# Interface.net
KiCad netlist of a schematic drawn in Altium Designer
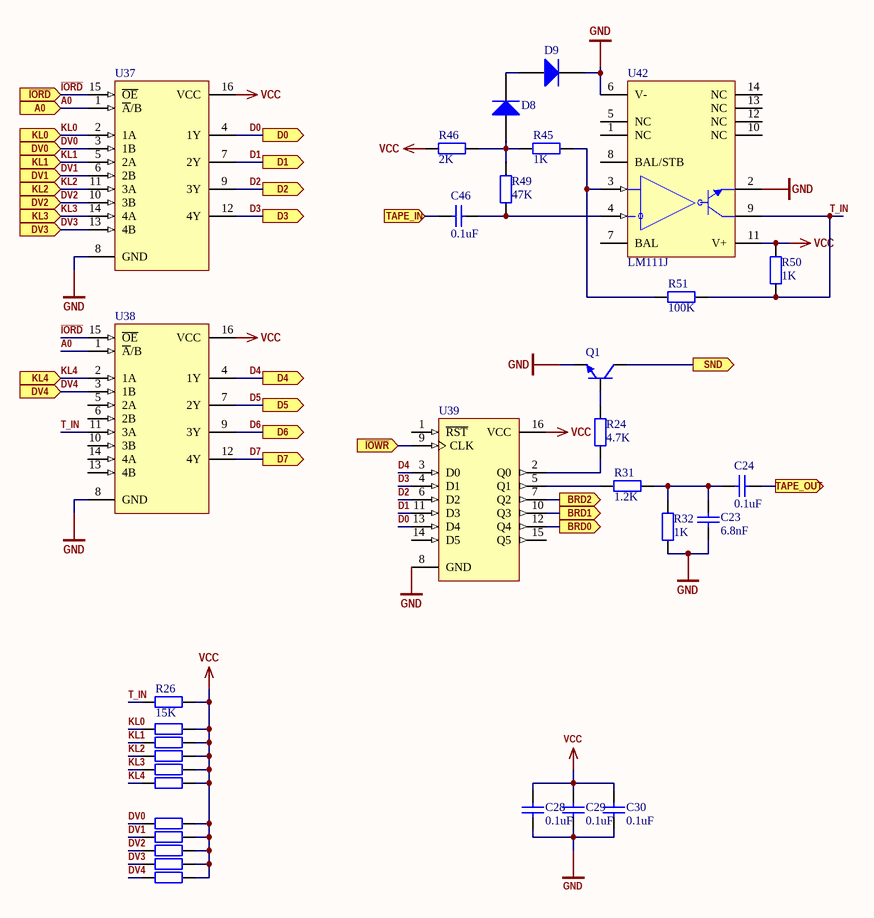
[diagram p0: Interface.SchDoc]

(export (version "E")
  (design (tool "Eeschema 10.0.6"))
  (components
    (comp (ref "C23")
      (value "6.8nF")
      (footprint "RAD-0.3")
      (description "Capacitor")
      (fields (field (name "Comment") "Cap") (field (name "PUBLISHER") "Altium Limited"))
      (libsource (lib "Lenin") (part "Cap"))
    )
    (comp (ref "C24")
      (value "0.1uF")
      (footprint "RAD-0.3")
      (description "Capacitor")
      (fields (field (name "Comment") "Cap") (field (name "PUBLISHER") "Altium Limited"))
      (libsource (lib "Lenin") (part "Cap"))
    )
    (comp (ref "C28")
      (value "0.1uF")
      (footprint "RAD-0.3")
      (description "Capacitor")
      (fields (field (name "Comment") "Cap") (field (name "PUBLISHER") "Altium Limited"))
      (libsource (lib "Lenin") (part "Cap"))
    )
    (comp (ref "C29")
      (value "0.1uF")
      (footprint "RAD-0.3")
      (description "Capacitor")
      (fields (field (name "Comment") "Cap") (field (name "PUBLISHER") "Altium Limited"))
      (libsource (lib "Lenin") (part "Cap"))
    )
    (comp (ref "C30")
      (value "0.1uF")
      (footprint "RAD-0.3")
      (description "Capacitor")
      (fields (field (name "Comment") "Cap") (field (name "PUBLISHER") "Altium Limited"))
      (libsource (lib "Lenin") (part "Cap"))
    )
    (comp (ref "C46")
      (value "0.1uF")
      (footprint "RAD-0.3")
      (description "Capacitor")
      (fields (field (name "Comment") "Cap") (field (name "PUBLISHER") "Altium Limited"))
      (libsource (lib "Lenin") (part "Cap"))
    )
    (comp (ref "D8")
      (value "Diode 1N4148")
      (footprint "DO-35")
      (description "High Conductance Fast Diode")
      (fields (field (name "PUBLISHER") "Altium Limited"))
      (libsource (lib "Miscellaneous Devices") (part "Diode 1N4148"))
    )
    (comp (ref "D9")
      (value "Diode 1N4148")
      (footprint "DO-35")
      (description "High Conductance Fast Diode")
      (fields (field (name "PUBLISHER") "Altium Limited"))
      (libsource (lib "Miscellaneous Devices") (part "Diode 1N4148"))
    )
    (comp (ref "Q1")
      (value "KT315")
      (footprint "Lenin:D35")
      (description "NPN General Purpose Amplifier")
      (fields (field (name "PUBLISHER") "Altium Limited"))
      (libsource (lib "Lenin") (part "KT315"))
    )
    (comp (ref "R24")
      (value "4.7K")
      (footprint "Lenin:AXIAL-0.4")
      (description "Resistor")
      (fields (field (name "Comment") "Res2") (field (name "PUBLISHER") "Altium Limited"))
      (libsource (lib "") (part "Res2_1"))
    )
    (comp (ref "R26")
      (value "15K")
      (footprint "Lenin:AXIAL-0.4")
      (description "Resistor")
      (fields (field (name "Comment") "Res2") (field (name "PUBLISHER") "Altium Limited"))
      (libsource (lib "Lenin") (part "Res2"))
    )
    (comp (ref "R27")
      (value "Res2")
      (footprint "Lenin:AXIAL-0.4")
      (description "Resistor")
      (fields (field (name "PUBLISHER") "Altium Limited"))
      (libsource (lib "Lenin") (part "Res2"))
    )
    (comp (ref "R28")
      (value "Res2")
      (footprint "Lenin:AXIAL-0.4")
      (description "Resistor")
      (fields (field (name "PUBLISHER") "Altium Limited"))
      (libsource (lib "Lenin") (part "Res2"))
    )
    (comp (ref "R29")
      (value "Res2")
      (footprint "Lenin:AXIAL-0.4")
      (description "Resistor")
      (fields (field (name "PUBLISHER") "Altium Limited"))
      (libsource (lib "Lenin") (part "Res2"))
    )
    (comp (ref "R30")
      (value "Res2")
      (footprint "Lenin:AXIAL-0.4")
      (description "Resistor")
      (fields (field (name "PUBLISHER") "Altium Limited"))
      (libsource (lib "Lenin") (part "Res2"))
    )
    (comp (ref "R31")
      (value "1.2K")
      (footprint "Lenin:AXIAL-0.4")
      (description "Resistor")
      (fields (field (name "Comment") "Res2") (field (name "PUBLISHER") "Altium Limited"))
      (libsource (lib "Lenin") (part "Res2"))
    )
    (comp (ref "R32")
      (value "1K")
      (footprint "Lenin:AXIAL-0.4")
      (description "Resistor")
      (fields (field (name "Comment") "Res2") (field (name "PUBLISHER") "Altium Limited"))
      (libsource (lib "") (part "Res2_1"))
    )
    (comp (ref "R33")
      (value "Res2")
      (footprint "Lenin:AXIAL-0.4")
      (description "Resistor")
      (fields (field (name "PUBLISHER") "Altium Limited"))
      (libsource (lib "Lenin") (part "Res2"))
    )
    (comp (ref "R36")
      (value "Res2")
      (footprint "Lenin:AXIAL-0.4")
      (description "Resistor")
      (fields (field (name "PUBLISHER") "Altium Limited"))
      (libsource (lib "Lenin") (part "Res2"))
    )
    (comp (ref "R38")
      (value "Res2")
      (footprint "Lenin:AXIAL-0.4")
      (description "Resistor")
      (fields (field (name "PUBLISHER") "Altium Limited"))
      (libsource (lib "Lenin") (part "Res2"))
    )
    (comp (ref "R40")
      (value "Res2")
      (footprint "Lenin:AXIAL-0.4")
      (description "Resistor")
      (fields (field (name "PUBLISHER") "Altium Limited"))
      (libsource (lib "Lenin") (part "Res2"))
    )
    (comp (ref "R42")
      (value "Res2")
      (footprint "Lenin:AXIAL-0.4")
      (description "Resistor")
      (fields (field (name "PUBLISHER") "Altium Limited"))
      (libsource (lib "Lenin") (part "Res2"))
    )
    (comp (ref "R44")
      (value "Res2")
      (footprint "Lenin:AXIAL-0.4")
      (description "Resistor")
      (fields (field (name "PUBLISHER") "Altium Limited"))
      (libsource (lib "Lenin") (part "Res2"))
    )
    (comp (ref "R45")
      (value "1K")
      (footprint "Lenin:AXIAL-0.4")
      (description "Resistor")
      (fields (field (name "Comment") "Res2") (field (name "PUBLISHER") "Altium Limited"))
      (libsource (lib "") (part "Res2_2"))
    )
    (comp (ref "R46")
      (value "2K")
      (footprint "Lenin:AXIAL-0.4")
      (description "Resistor")
      (fields (field (name "Comment") "Res2") (field (name "PUBLISHER") "Altium Limited"))
      (libsource (lib "") (part "Res2_2"))
    )
    (comp (ref "R49")
      (value "47K")
      (footprint "Lenin:AXIAL-0.4")
      (description "Resistor")
      (fields (field (name "Comment") "Res2") (field (name "PUBLISHER") "Altium Limited"))
      (libsource (lib "Lenin") (part "Res2"))
    )
    (comp (ref "R50")
      (value "1K")
      (footprint "Lenin:AXIAL-0.4")
      (description "Resistor")
      (fields (field (name "Comment") "Res2") (field (name "PUBLISHER") "Altium Limited"))
      (libsource (lib "Lenin") (part "Res2"))
    )
    (comp (ref "R51")
      (value "100K")
      (footprint "Lenin:AXIAL-0.4")
      (description "Resistor")
      (fields (field (name "Comment") "Res2") (field (name "PUBLISHER") "Altium Limited"))
      (libsource (lib "") (part "Res2_2"))
    )
    (comp (ref "U37")
      (value "~")
      (footprint "N016")
      (description "Quadruple 2-Line to 1-Line Data Selector/Multiplexer with 3-State Outputs")
      (fields (field (name "PUBLISHER") "Altium Limited"))
      (libsource (lib "TI Logic Multiplexer") (part "SN74HC257N"))
    )
    (comp (ref "U38")
      (value "~")
      (footprint "N016")
      (description "Quadruple 2-Line to 1-Line Data Selector/Multiplexer with 3-State Outputs")
      (fields (field (name "PUBLISHER") "Altium Limited"))
      (libsource (lib "TI Logic Multiplexer") (part "SN74HC257N"))
    )
    (comp (ref "U39")
      (value "~")
      (footprint "N016")
      (description "Hex D-Type Flip-Flop with Clear")
      (fields (field (name "PUBLISHER") "Altium Limited"))
      (libsource (lib "TI Logic Flip-Flop") (part "SN74HC174N"))
    )
    (comp (ref "U42")
      (value "LM111J")
      (footprint "J014")
      (description "Differential Comparator with Strobe")
      (fields (field (name "PUBLISHER") "Altium Limited"))
      (libsource (lib "TI Analog Comparator") (part "LM111J"))
    )
  )
  (nets
    (net (code "1") (name "/A0") (class "Default")
      (node (ref "U37") (pin "1") (pinfunction "~{A}/B_1") (pintype "input"))
      (node (ref "U38") (pin "1") (pinfunction "~{A}/B_1") (pintype "input"))
    )
    (net (code "2") (name "/BRD0") (class "Default")
      (node (ref "U39") (pin "12") (pinfunction "Q4_12") (pintype "output"))
    )
    (net (code "3") (name "/BRD1") (class "Default")
      (node (ref "U39") (pin "10") (pinfunction "Q3_10") (pintype "output"))
    )
    (net (code "4") (name "/BRD2") (class "Default")
      (node (ref "U39") (pin "7") (pinfunction "Q2_7") (pintype "output"))
    )
    (net (code "5") (name "/D0") (class "Default")
      (node (ref "U37") (pin "4") (pinfunction "1Y_4") (pintype "tri_state"))
      (node (ref "U39") (pin "13") (pinfunction "D4_13") (pintype "input"))
    )
    (net (code "6") (name "/D1") (class "Default")
      (node (ref "U37") (pin "7") (pinfunction "2Y_7") (pintype "tri_state"))
      (node (ref "U39") (pin "11") (pinfunction "D3_11") (pintype "input"))
    )
    (net (code "7") (name "/D2") (class "Default")
      (node (ref "U37") (pin "9") (pinfunction "3Y_9") (pintype "tri_state"))
      (node (ref "U39") (pin "6") (pinfunction "D2_6") (pintype "input"))
    )
    (net (code "8") (name "/D3") (class "Default")
      (node (ref "U37") (pin "12") (pinfunction "4Y_12") (pintype "tri_state"))
      (node (ref "U39") (pin "4") (pinfunction "D1_4") (pintype "input"))
    )
    (net (code "9") (name "/D4") (class "Default")
      (node (ref "U38") (pin "4") (pinfunction "1Y_4") (pintype "tri_state"))
      (node (ref "U39") (pin "3") (pinfunction "D0_3") (pintype "input"))
    )
    (net (code "10") (name "/D5") (class "Default")
      (node (ref "U38") (pin "7") (pinfunction "2Y_7") (pintype "tri_state"))
    )
    (net (code "11") (name "/D6") (class "Default")
      (node (ref "U38") (pin "9") (pinfunction "3Y_9") (pintype "tri_state"))
    )
    (net (code "12") (name "/D7") (class "Default")
      (node (ref "U38") (pin "12") (pinfunction "4Y_12") (pintype "tri_state"))
    )
    (net (code "13") (name "/DV0") (class "Default")
      (node (ref "R36") (pin "1") (pinfunction "1_1") (pintype "passive"))
      (node (ref "U37") (pin "3") (pinfunction "1B_3") (pintype "input"))
    )
    (net (code "14") (name "/DV1") (class "Default")
      (node (ref "R38") (pin "1") (pinfunction "1_1") (pintype "passive"))
      (node (ref "U37") (pin "6") (pinfunction "2B_6") (pintype "input"))
    )
    (net (code "15") (name "/DV2") (class "Default")
      (node (ref "R40") (pin "1") (pinfunction "1_1") (pintype "passive"))
      (node (ref "U37") (pin "10") (pinfunction "3B_10") (pintype "input"))
    )
    (net (code "16") (name "/DV3") (class "Default")
      (node (ref "R42") (pin "1") (pinfunction "1_1") (pintype "passive"))
      (node (ref "U37") (pin "13") (pinfunction "4B_13") (pintype "input"))
    )
    (net (code "17") (name "/DV4") (class "Default")
      (node (ref "R44") (pin "1") (pinfunction "1_1") (pintype "passive"))
      (node (ref "U38") (pin "3") (pinfunction "1B_3") (pintype "input"))
    )
    (net (code "18") (name "/KL0") (class "Default")
      (node (ref "R27") (pin "1") (pinfunction "1_1") (pintype "passive"))
      (node (ref "U37") (pin "2") (pinfunction "1A_2") (pintype "input"))
    )
    (net (code "19") (name "/KL1") (class "Default")
      (node (ref "R28") (pin "1") (pinfunction "1_1") (pintype "passive"))
      (node (ref "U37") (pin "5") (pinfunction "2A_5") (pintype "input"))
    )
    (net (code "20") (name "/KL2") (class "Default")
      (node (ref "R29") (pin "1") (pinfunction "1_1") (pintype "passive"))
      (node (ref "U37") (pin "11") (pinfunction "3A_11") (pintype "input"))
    )
    (net (code "21") (name "/KL3") (class "Default")
      (node (ref "R30") (pin "1") (pinfunction "1_1") (pintype "passive"))
      (node (ref "U37") (pin "14") (pinfunction "4A_14") (pintype "input"))
    )
    (net (code "22") (name "/KL4") (class "Default")
      (node (ref "R33") (pin "1") (pinfunction "1_1") (pintype "passive"))
      (node (ref "U38") (pin "2") (pinfunction "1A_2") (pintype "input"))
    )
    (net (code "23") (name "/SND") (class "Default")
      (node (ref "Q1") (pin "2") (pinfunction "C_2") (pintype "passive"))
    )
    (net (code "24") (name "/TAPE_IN") (class "Default")
      (node (ref "C46") (pin "1") (pinfunction "1_1") (pintype "passive"))
    )
    (net (code "25") (name "/TAPE_OUT") (class "Default")
      (node (ref "C24") (pin "1") (pinfunction "1_1") (pintype "passive"))
    )
    (net (code "26") (name "/T_IN") (class "Default")
      (node (ref "R26") (pin "1") (pinfunction "1_1") (pintype "passive"))
      (node (ref "R50") (pin "1") (pinfunction "1_1") (pintype "passive"))
      (node (ref "R51") (pin "1") (pinfunction "1_1") (pintype "passive"))
      (node (ref "U38") (pin "11") (pinfunction "3A_11") (pintype "input"))
      (node (ref "U42") (pin "9") (pinfunction "COL_OUT_9") (pintype "passive"))
    )
    (net (code "27") (name "/~{IORD}") (class "Default")
      (node (ref "U37") (pin "15") (pinfunction "~{OE}_15") (pintype "input"))
      (node (ref "U38") (pin "15") (pinfunction "~{OE}_15") (pintype "input"))
    )
    (net (code "28") (name "/~{IOWR}") (class "Default")
      (node (ref "U39") (pin "9") (pinfunction "CLK_9") (pintype "input"))
    )
    (net (code "29") (name "GND") (class "Default")
      (node (ref "C23") (pin "1") (pinfunction "1_1") (pintype "passive"))
      (node (ref "C28") (pin "1") (pinfunction "1_1") (pintype "passive"))
      (node (ref "C29") (pin "1") (pinfunction "1_1") (pintype "passive"))
      (node (ref "C30") (pin "1") (pinfunction "1_1") (pintype "passive"))
      (node (ref "D9") (pin "2") (pinfunction "K_2") (pintype "passive"))
      (node (ref "Q1") (pin "1") (pinfunction "E_1") (pintype "passive"))
      (node (ref "R32") (pin "1") (pinfunction "1_1") (pintype "passive"))
      (node (ref "U37") (pin "8") (pinfunction "GND_8") (pintype "power_in"))
      (node (ref "U38") (pin "8") (pinfunction "GND_8") (pintype "power_in"))
      (node (ref "U39") (pin "8") (pinfunction "GND_8") (pintype "power_in"))
      (node (ref "U42") (pin "2") (pinfunction "EM_OUT_2") (pintype "passive"))
      (node (ref "U42") (pin "6") (pinfunction "V-_6") (pintype "power_in"))
    )
    (net (code "30") (name "Net-(C23-Pad2)") (class "Default")
      (node (ref "C23") (pin "2") (pinfunction "2_2") (pintype "passive"))
      (node (ref "C24") (pin "2") (pinfunction "2_2") (pintype "passive"))
      (node (ref "R31") (pin "2") (pinfunction "2_2") (pintype "passive"))
      (node (ref "R32") (pin "2") (pinfunction "2_2") (pintype "passive"))
    )
    (net (code "31") (name "Net-(D8-A)") (class "Default")
      (node (ref "D8") (pin "1") (pinfunction "A_1") (pintype "passive"))
      (node (ref "R45") (pin "2") (pinfunction "2_2") (pintype "passive"))
      (node (ref "R46") (pin "1") (pinfunction "1_1") (pintype "passive"))
      (node (ref "R49") (pin "2") (pinfunction "2_2") (pintype "passive"))
    )
    (net (code "32") (name "Net-(D8-K)") (class "Default")
      (node (ref "D8") (pin "2") (pinfunction "K_2") (pintype "passive"))
      (node (ref "D9") (pin "1") (pinfunction "A_1") (pintype "passive"))
    )
    (net (code "33") (name "Net-(Q1-B)") (class "Default")
      (node (ref "Q1") (pin "3") (pinfunction "B_3") (pintype "passive"))
      (node (ref "R24") (pin "2") (pinfunction "2_2") (pintype "passive"))
    )
    (net (code "34") (name "Net-(U39-Q0)") (class "Default")
      (node (ref "R24") (pin "1") (pinfunction "1_1") (pintype "passive"))
      (node (ref "U39") (pin "2") (pinfunction "Q0_2") (pintype "output"))
    )
    (net (code "35") (name "Net-(U39-Q1)") (class "Default")
      (node (ref "R31") (pin "1") (pinfunction "1_1") (pintype "passive"))
      (node (ref "U39") (pin "5") (pinfunction "Q1_5") (pintype "output"))
    )
    (net (code "36") (name "Net-(U42-IN+)") (class "Default")
      (node (ref "R45") (pin "1") (pinfunction "1_1") (pintype "passive"))
      (node (ref "R51") (pin "2") (pinfunction "2_2") (pintype "passive"))
      (node (ref "U42") (pin "3") (pinfunction "IN+_3") (pintype "input"))
    )
    (net (code "37") (name "Net-(U42-IN-)") (class "Default")
      (node (ref "C46") (pin "2") (pinfunction "2_2") (pintype "passive"))
      (node (ref "R49") (pin "1") (pinfunction "1_1") (pintype "passive"))
      (node (ref "U42") (pin "4") (pinfunction "IN-_4") (pintype "input"))
    )
    (net (code "38") (name "VCC") (class "Default")
      (node (ref "C28") (pin "2") (pinfunction "2_2") (pintype "passive"))
      (node (ref "C29") (pin "2") (pinfunction "2_2") (pintype "passive"))
      (node (ref "C30") (pin "2") (pinfunction "2_2") (pintype "passive"))
      (node (ref "R26") (pin "2") (pinfunction "2_2") (pintype "passive"))
      (node (ref "R27") (pin "2") (pinfunction "2_2") (pintype "passive"))
      (node (ref "R28") (pin "2") (pinfunction "2_2") (pintype "passive"))
      (node (ref "R29") (pin "2") (pinfunction "2_2") (pintype "passive"))
      (node (ref "R30") (pin "2") (pinfunction "2_2") (pintype "passive"))
      (node (ref "R33") (pin "2") (pinfunction "2_2") (pintype "passive"))
      (node (ref "R36") (pin "2") (pinfunction "2_2") (pintype "passive"))
      (node (ref "R38") (pin "2") (pinfunction "2_2") (pintype "passive"))
      (node (ref "R40") (pin "2") (pinfunction "2_2") (pintype "passive"))
      (node (ref "R42") (pin "2") (pinfunction "2_2") (pintype "passive"))
      (node (ref "R44") (pin "2") (pinfunction "2_2") (pintype "passive"))
      (node (ref "R46") (pin "2") (pinfunction "2_2") (pintype "passive"))
      (node (ref "R50") (pin "2") (pinfunction "2_2") (pintype "passive"))
      (node (ref "U37") (pin "16") (pinfunction "VCC_16") (pintype "power_in"))
      (node (ref "U38") (pin "16") (pinfunction "VCC_16") (pintype "power_in"))
      (node (ref "U39") (pin "16") (pinfunction "VCC_16") (pintype "power_in"))
      (node (ref "U42") (pin "11") (pinfunction "V+_11") (pintype "power_in"))
    )
    (net (code "39") (name "unconnected-(U38-2A-Pad5)") (class "Default")
      (node (ref "U38") (pin "5") (pinfunction "2A_5") (pintype "input"))
    )
    (net (code "40") (name "unconnected-(U38-2B-Pad6)") (class "Default")
      (node (ref "U38") (pin "6") (pinfunction "2B_6") (pintype "input"))
    )
    (net (code "41") (name "unconnected-(U38-3B-Pad10)") (class "Default")
      (node (ref "U38") (pin "10") (pinfunction "3B_10") (pintype "input"))
    )
    (net (code "42") (name "unconnected-(U38-4A-Pad14)") (class "Default")
      (node (ref "U38") (pin "14") (pinfunction "4A_14") (pintype "input"))
    )
    (net (code "43") (name "unconnected-(U38-4B-Pad13)") (class "Default")
      (node (ref "U38") (pin "13") (pinfunction "4B_13") (pintype "input"))
    )
    (net (code "44") (name "unconnected-(U39-D5-Pad14)") (class "Default")
      (node (ref "U39") (pin "14") (pinfunction "D5_14") (pintype "input"))
    )
    (net (code "45") (name "unconnected-(U39-Q5-Pad15)") (class "Default")
      (node (ref "U39") (pin "15") (pinfunction "Q5_15") (pintype "output"))
    )
    (net (code "46") (name "unconnected-(U39-~{RST}-Pad1)") (class "Default")
      (node (ref "U39") (pin "1") (pinfunction "~{RST}_1") (pintype "input"))
    )
    (net (code "47") (name "unconnected-(U42-BAL-Pad7)") (class "Default")
      (node (ref "U42") (pin "7") (pinfunction "BAL_7") (pintype "passive"))
    )
    (net (code "48") (name "unconnected-(U42-BAL{slash}STB-Pad8)") (class "Default")
      (node (ref "U42") (pin "8") (pinfunction "BAL/STB_8") (pintype "passive"))
    )
    (net (code "49") (name "unconnected-(U42-NC-Pad1)") (class "Default")
      (node (ref "U42") (pin "1") (pinfunction "NC_1") (pintype "passive"))
    )
    (net (code "50") (name "unconnected-(U42-NC-Pad5)") (class "Default")
      (node (ref "U42") (pin "5") (pinfunction "NC_5") (pintype "passive"))
    )
    (net (code "51") (name "unconnected-(U42-NC-Pad10)") (class "Default")
      (node (ref "U42") (pin "10") (pinfunction "NC_10") (pintype "passive"))
    )
    (net (code "52") (name "unconnected-(U42-NC-Pad12)") (class "Default")
      (node (ref "U42") (pin "12") (pinfunction "NC_12") (pintype "passive"))
    )
    (net (code "53") (name "unconnected-(U42-NC-Pad13)") (class "Default")
      (node (ref "U42") (pin "13") (pinfunction "NC_13") (pintype "passive"))
    )
    (net (code "54") (name "unconnected-(U42-NC-Pad14)") (class "Default")
      (node (ref "U42") (pin "14") (pinfunction "NC_14") (pintype "passive"))
    )
  )
)
